# IC_Adapter_2x20.net
KiCad netlist of a schematic drawn in EAGLE
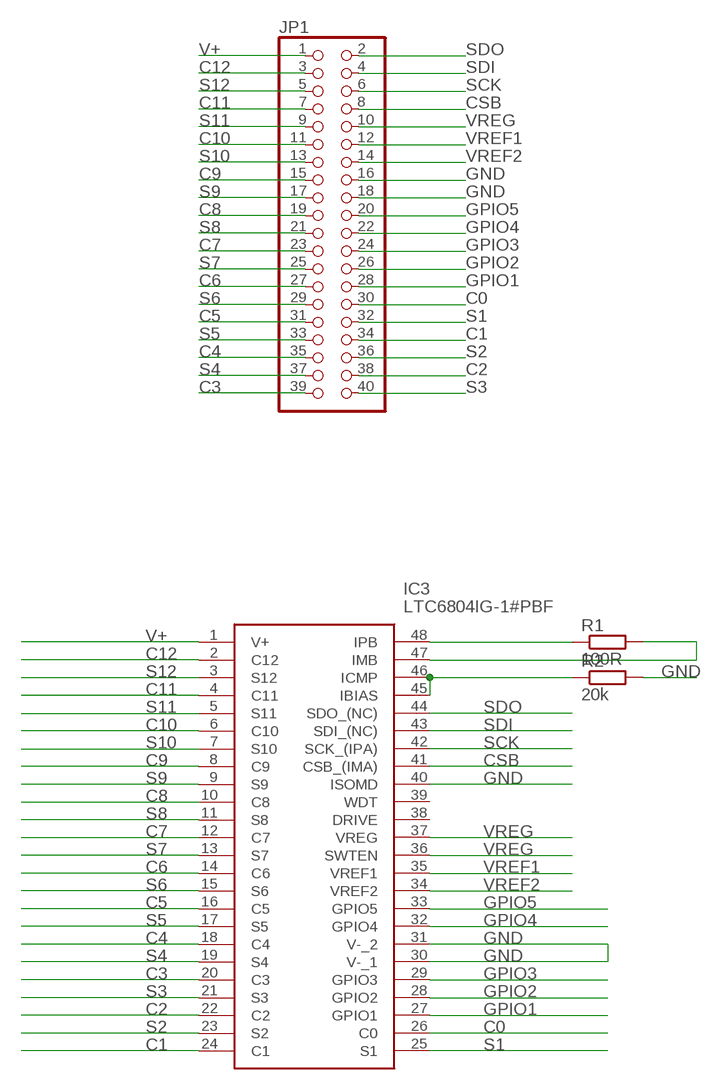
[diagram p0: schematic, sheet 1]

(export (version "E")
  (design (tool "Eeschema 10.0.6"))
  (components
    (comp (ref "IC3")
      (value "LTC6804IG-1#PBF")
      (footprint "eagle-import:SOP50P780X200-48N")
      (fields (field (name "MOUSER_PART_NUMBER") "584-LTC6804IG-1#PBF"))
      (libsource (lib "eagle-import") (part "LTC6804IG-1#PBF"))
    )
    (comp (ref "JP1")
      (value "PINHD-2X20")
      (footprint "eagle-import:2X20")
      (libsource (lib "eagle-import") (part "PINHD-2X20"))
    )
    (comp (ref "R1")
      (value "100R")
      (footprint "eagle-import:R0805")
      (libsource (lib "eagle-import") (part "R-EU_R0805"))
    )
    (comp (ref "R2")
      (value "20k")
      (footprint "eagle-import:R0805")
      (libsource (lib "eagle-import") (part "R-EU_R0805"))
    )
  )
  (nets
    (net (code "1") (name "/C0") (class "Default")
      (node (ref "IC3") (pin "26") (pinfunction "C0_26") (pintype "bidirectional"))
      (node (ref "JP1") (pin "30") (pinfunction "30_30") (pintype "passive"))
    )
    (net (code "2") (name "/C1") (class "Default")
      (node (ref "IC3") (pin "24") (pinfunction "C1_24") (pintype "bidirectional"))
      (node (ref "JP1") (pin "34") (pinfunction "34_34") (pintype "passive"))
    )
    (net (code "3") (name "/C2") (class "Default")
      (node (ref "IC3") (pin "22") (pinfunction "C2_22") (pintype "bidirectional"))
      (node (ref "JP1") (pin "38") (pinfunction "38_38") (pintype "passive"))
    )
    (net (code "4") (name "/C3") (class "Default")
      (node (ref "IC3") (pin "20") (pinfunction "C3_20") (pintype "bidirectional"))
      (node (ref "JP1") (pin "39") (pinfunction "39_39") (pintype "passive"))
    )
    (net (code "5") (name "/C4") (class "Default")
      (node (ref "IC3") (pin "18") (pinfunction "C4_18") (pintype "bidirectional"))
      (node (ref "JP1") (pin "35") (pinfunction "35_35") (pintype "passive"))
    )
    (net (code "6") (name "/C5") (class "Default")
      (node (ref "IC3") (pin "16") (pinfunction "C5_16") (pintype "bidirectional"))
      (node (ref "JP1") (pin "31") (pinfunction "31_31") (pintype "passive"))
    )
    (net (code "7") (name "/C6") (class "Default")
      (node (ref "IC3") (pin "14") (pinfunction "C6_14") (pintype "bidirectional"))
      (node (ref "JP1") (pin "27") (pinfunction "27_27") (pintype "passive"))
    )
    (net (code "8") (name "/C7") (class "Default")
      (node (ref "IC3") (pin "12") (pinfunction "C7_12") (pintype "bidirectional"))
      (node (ref "JP1") (pin "23") (pinfunction "23_23") (pintype "passive"))
    )
    (net (code "9") (name "/C8") (class "Default")
      (node (ref "IC3") (pin "10") (pinfunction "C8_10") (pintype "bidirectional"))
      (node (ref "JP1") (pin "19") (pinfunction "19_19") (pintype "passive"))
    )
    (net (code "10") (name "/C9") (class "Default")
      (node (ref "IC3") (pin "8") (pinfunction "C9_8") (pintype "bidirectional"))
      (node (ref "JP1") (pin "15") (pinfunction "15_15") (pintype "passive"))
    )
    (net (code "11") (name "/C10") (class "Default")
      (node (ref "IC3") (pin "6") (pinfunction "C10_6") (pintype "bidirectional"))
      (node (ref "JP1") (pin "11") (pinfunction "11_11") (pintype "passive"))
    )
    (net (code "12") (name "/C11") (class "Default")
      (node (ref "IC3") (pin "4") (pinfunction "C11_4") (pintype "bidirectional"))
      (node (ref "JP1") (pin "7") (pinfunction "7_7") (pintype "passive"))
    )
    (net (code "13") (name "/C12") (class "Default")
      (node (ref "IC3") (pin "2") (pinfunction "C12_2") (pintype "bidirectional"))
      (node (ref "JP1") (pin "3") (pinfunction "3_3") (pintype "passive"))
    )
    (net (code "14") (name "/CSB") (class "Default")
      (node (ref "IC3") (pin "41") (pinfunction "CSB_(IMA)_41") (pintype "bidirectional"))
      (node (ref "JP1") (pin "8") (pinfunction "8_8") (pintype "passive"))
    )
    (net (code "15") (name "/GND") (class "Default")
      (node (ref "IC3") (pin "30") (pinfunction "V-_1_30") (pintype "bidirectional"))
      (node (ref "IC3") (pin "31") (pinfunction "V-_2_31") (pintype "bidirectional"))
      (node (ref "IC3") (pin "40") (pinfunction "ISOMD_40") (pintype "bidirectional"))
      (node (ref "JP1") (pin "16") (pinfunction "16_16") (pintype "passive"))
      (node (ref "JP1") (pin "18") (pinfunction "18_18") (pintype "passive"))
      (node (ref "R2") (pin "2") (pinfunction "2_2") (pintype "passive"))
    )
    (net (code "16") (name "/GPIO1") (class "Default")
      (node (ref "IC3") (pin "27") (pinfunction "GPIO1_27") (pintype "bidirectional"))
      (node (ref "JP1") (pin "28") (pinfunction "28_28") (pintype "passive"))
    )
    (net (code "17") (name "/GPIO2") (class "Default")
      (node (ref "IC3") (pin "28") (pinfunction "GPIO2_28") (pintype "bidirectional"))
      (node (ref "JP1") (pin "26") (pinfunction "26_26") (pintype "passive"))
    )
    (net (code "18") (name "/GPIO3") (class "Default")
      (node (ref "IC3") (pin "29") (pinfunction "GPIO3_29") (pintype "bidirectional"))
      (node (ref "JP1") (pin "24") (pinfunction "24_24") (pintype "passive"))
    )
    (net (code "19") (name "/GPIO4") (class "Default")
      (node (ref "IC3") (pin "32") (pinfunction "GPIO4_32") (pintype "bidirectional"))
      (node (ref "JP1") (pin "22") (pinfunction "22_22") (pintype "passive"))
    )
    (net (code "20") (name "/GPIO5") (class "Default")
      (node (ref "IC3") (pin "33") (pinfunction "GPIO5_33") (pintype "bidirectional"))
      (node (ref "JP1") (pin "20") (pinfunction "20_20") (pintype "passive"))
    )
    (net (code "21") (name "/S1") (class "Default")
      (node (ref "IC3") (pin "25") (pinfunction "S1_25") (pintype "bidirectional"))
      (node (ref "JP1") (pin "32") (pinfunction "32_32") (pintype "passive"))
    )
    (net (code "22") (name "/S2") (class "Default")
      (node (ref "IC3") (pin "23") (pinfunction "S2_23") (pintype "bidirectional"))
      (node (ref "JP1") (pin "36") (pinfunction "36_36") (pintype "passive"))
    )
    (net (code "23") (name "/S3") (class "Default")
      (node (ref "IC3") (pin "21") (pinfunction "S3_21") (pintype "bidirectional"))
      (node (ref "JP1") (pin "40") (pinfunction "40_40") (pintype "passive"))
    )
    (net (code "24") (name "/S4") (class "Default")
      (node (ref "IC3") (pin "19") (pinfunction "S4_19") (pintype "bidirectional"))
      (node (ref "JP1") (pin "37") (pinfunction "37_37") (pintype "passive"))
    )
    (net (code "25") (name "/S5") (class "Default")
      (node (ref "IC3") (pin "17") (pinfunction "S5_17") (pintype "bidirectional"))
      (node (ref "JP1") (pin "33") (pinfunction "33_33") (pintype "passive"))
    )
    (net (code "26") (name "/S6") (class "Default")
      (node (ref "IC3") (pin "15") (pinfunction "S6_15") (pintype "bidirectional"))
      (node (ref "JP1") (pin "29") (pinfunction "29_29") (pintype "passive"))
    )
    (net (code "27") (name "/S7") (class "Default")
      (node (ref "IC3") (pin "13") (pinfunction "S7_13") (pintype "bidirectional"))
      (node (ref "JP1") (pin "25") (pinfunction "25_25") (pintype "passive"))
    )
    (net (code "28") (name "/S8") (class "Default")
      (node (ref "IC3") (pin "11") (pinfunction "S8_11") (pintype "bidirectional"))
      (node (ref "JP1") (pin "21") (pinfunction "21_21") (pintype "passive"))
    )
    (net (code "29") (name "/S9") (class "Default")
      (node (ref "IC3") (pin "9") (pinfunction "S9_9") (pintype "bidirectional"))
      (node (ref "JP1") (pin "17") (pinfunction "17_17") (pintype "passive"))
    )
    (net (code "30") (name "/S10") (class "Default")
      (node (ref "IC3") (pin "7") (pinfunction "S10_7") (pintype "bidirectional"))
      (node (ref "JP1") (pin "13") (pinfunction "13_13") (pintype "passive"))
    )
    (net (code "31") (name "/S11") (class "Default")
      (node (ref "IC3") (pin "5") (pinfunction "S11_5") (pintype "bidirectional"))
      (node (ref "JP1") (pin "9") (pinfunction "9_9") (pintype "passive"))
    )
    (net (code "32") (name "/S12") (class "Default")
      (node (ref "IC3") (pin "3") (pinfunction "S12_3") (pintype "bidirectional"))
      (node (ref "JP1") (pin "5") (pinfunction "5_5") (pintype "passive"))
    )
    (net (code "33") (name "/SCK") (class "Default")
      (node (ref "IC3") (pin "42") (pinfunction "SCK_(IPA)_42") (pintype "bidirectional"))
      (node (ref "JP1") (pin "6") (pinfunction "6_6") (pintype "passive"))
    )
    (net (code "34") (name "/SDI") (class "Default")
      (node (ref "IC3") (pin "43") (pinfunction "SDI_(NC)_43") (pintype "bidirectional"))
      (node (ref "JP1") (pin "4") (pinfunction "4_4") (pintype "passive"))
    )
    (net (code "35") (name "/SDO") (class "Default")
      (node (ref "IC3") (pin "44") (pinfunction "SDO_(NC)_44") (pintype "bidirectional"))
      (node (ref "JP1") (pin "2") (pinfunction "2_2") (pintype "passive"))
    )
    (net (code "36") (name "/V+") (class "Default")
      (node (ref "IC3") (pin "1") (pinfunction "V+_1") (pintype "bidirectional"))
      (node (ref "JP1") (pin "1") (pinfunction "1_1") (pintype "passive"))
    )
    (net (code "37") (name "/VREF1") (class "Default")
      (node (ref "IC3") (pin "35") (pinfunction "VREF1_35") (pintype "bidirectional"))
      (node (ref "JP1") (pin "12") (pinfunction "12_12") (pintype "passive"))
    )
    (net (code "38") (name "/VREF2") (class "Default")
      (node (ref "IC3") (pin "34") (pinfunction "VREF2_34") (pintype "bidirectional"))
      (node (ref "JP1") (pin "14") (pinfunction "14_14") (pintype "passive"))
    )
    (net (code "39") (name "/VREG") (class "Default")
      (node (ref "IC3") (pin "36") (pinfunction "SWTEN_36") (pintype "bidirectional"))
      (node (ref "IC3") (pin "37") (pinfunction "VREG_37") (pintype "bidirectional"))
      (node (ref "JP1") (pin "10") (pinfunction "10_10") (pintype "passive"))
    )
    (net (code "40") (name "Net-(IC3-IBIAS)") (class "Default")
      (node (ref "IC3") (pin "45") (pinfunction "IBIAS_45") (pintype "bidirectional"))
      (node (ref "IC3") (pin "46") (pinfunction "ICMP_46") (pintype "bidirectional"))
      (node (ref "R2") (pin "1") (pinfunction "1_1") (pintype "passive"))
    )
    (net (code "41") (name "Net-(IC3-IMB)") (class "Default")
      (node (ref "IC3") (pin "47") (pinfunction "IMB_47") (pintype "bidirectional"))
      (node (ref "R1") (pin "2") (pinfunction "2_2") (pintype "passive"))
    )
    (net (code "42") (name "Net-(IC3-IPB)") (class "Default")
      (node (ref "IC3") (pin "48") (pinfunction "IPB_48") (pintype "bidirectional"))
      (node (ref "R1") (pin "1") (pinfunction "1_1") (pintype "passive"))
    )
    (net (code "43") (name "unconnected-(IC3-DRIVE-Pad38)") (class "Default")
      (node (ref "IC3") (pin "38") (pinfunction "DRIVE_38") (pintype "bidirectional"))
    )
    (net (code "44") (name "unconnected-(IC3-WDT-Pad39)") (class "Default")
      (node (ref "IC3") (pin "39") (pinfunction "WDT_39") (pintype "bidirectional"))
    )
  )
)
